# BMS-Shield_rev3.net
KiCad netlist of a schematic drawn in EAGLE
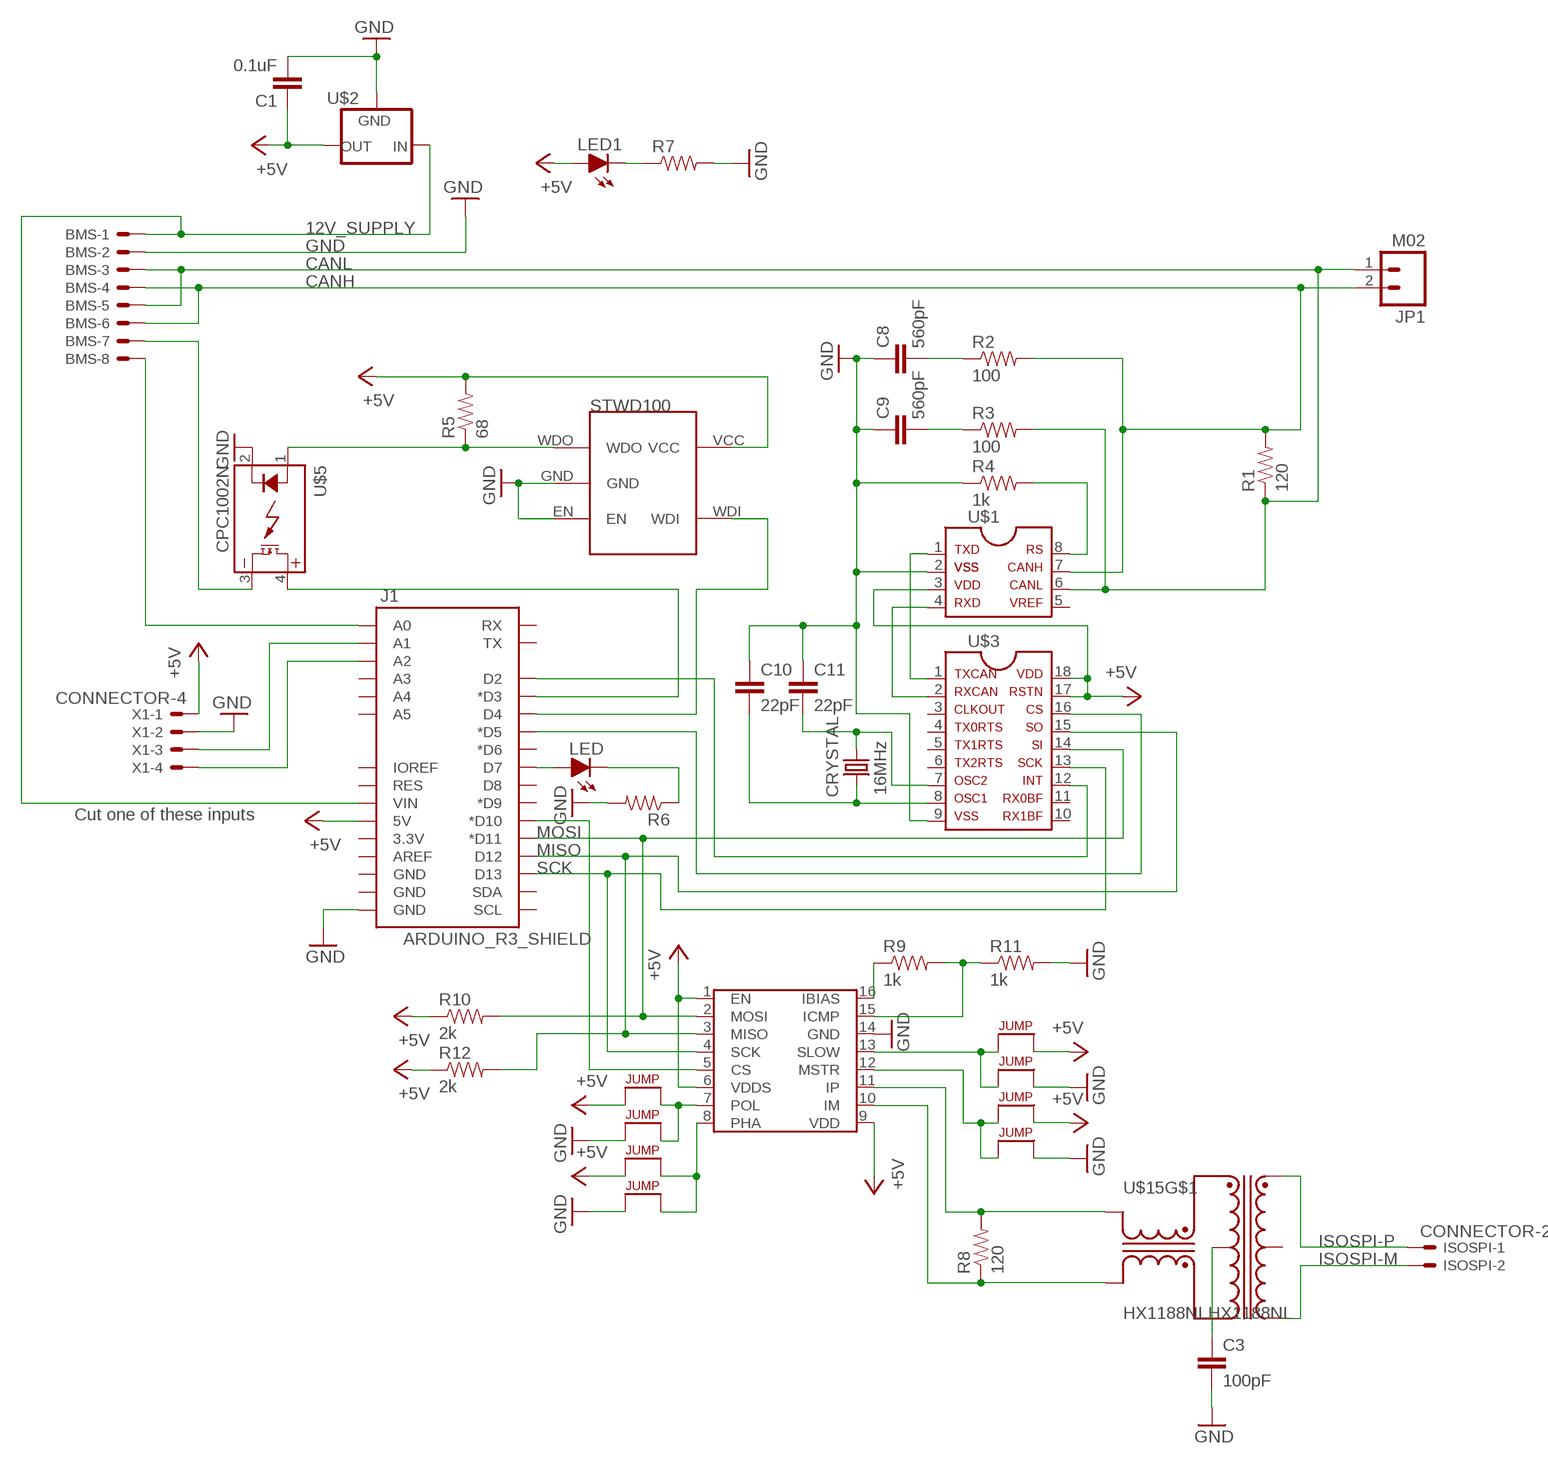
[diagram p0: schematic, sheet 1]

(export (version "E")
  (design (tool "Eeschema 10.0.6"))
  (components
    (comp (ref "BMS")
      (value "MINIFIT_5566-8")
      (footprint "eagle-import:MINIFIT_5566-8")
      (libsource (lib "eagle-import") (part "MINIFIT_5566-8"))
    )
    (comp (ref "C1")
      (value "0.1uF")
      (footprint "eagle-import:0805")
      (libsource (lib "eagle-import") (part "CAP0805"))
    )
    (comp (ref "C3")
      (value "100pF")
      (footprint "eagle-import:0805")
      (libsource (lib "eagle-import") (part "CAP0805"))
    )
    (comp (ref "C8")
      (value "560pF")
      (footprint "eagle-import:0805")
      (libsource (lib "eagle-import") (part "CAP0805"))
    )
    (comp (ref "C9")
      (value "560pF")
      (footprint "eagle-import:0805")
      (libsource (lib "eagle-import") (part "CAP0805"))
    )
    (comp (ref "C10")
      (value "22pF")
      (footprint "eagle-import:0805")
      (libsource (lib "eagle-import") (part "CAP0805"))
    )
    (comp (ref "C11")
      (value "22pF")
      (footprint "eagle-import:0805")
      (libsource (lib "eagle-import") (part "CAP0805"))
    )
    (comp (ref "CRYSTAL")
      (value "16MHz")
      (footprint "eagle-import:HC49UP")
      (libsource (lib "eagle-import") (part "CRYSTALSMD"))
    )
    (comp (ref "ISOSPI")
      (value "CONNECTOR-2")
      (footprint "eagle-import:MINIFIT_5566-2")
      (libsource (lib "eagle-import") (part "CONNECTOR-2"))
    )
    (comp (ref "J1")
      (value "ARDUINO_R3_SHIELD")
      (footprint "eagle-import:UNO_R3_SHIELD")
      (libsource (lib "eagle-import") (part "ARDUINO_R3_SHIELD"))
    )
    (comp (ref "JP1")
      (value "M02")
      (footprint "eagle-import:1X02")
      (libsource (lib "eagle-import") (part "M02"))
    )
    (comp (ref "LED")
      (value "LED-0805")
      (footprint "eagle-import:LED-805")
      (libsource (lib "eagle-import") (part "LED-0805"))
    )
    (comp (ref "LED1")
      (value "LED-0805")
      (footprint "eagle-import:LED-805")
      (libsource (lib "eagle-import") (part "LED-0805"))
    )
    (comp (ref "R1")
      (value "120")
      (footprint "eagle-import:0805")
      (libsource (lib "eagle-import") (part "RESISTOR0805-RES"))
    )
    (comp (ref "R2")
      (value "100")
      (footprint "eagle-import:0805")
      (libsource (lib "eagle-import") (part "RESISTOR0805-RES"))
    )
    (comp (ref "R3")
      (value "100")
      (footprint "eagle-import:0805")
      (libsource (lib "eagle-import") (part "RESISTOR0805-RES"))
    )
    (comp (ref "R4")
      (value "1k")
      (footprint "eagle-import:0805")
      (libsource (lib "eagle-import") (part "RESISTOR0805-RES"))
    )
    (comp (ref "R5")
      (value "68")
      (footprint "eagle-import:0805")
      (libsource (lib "eagle-import") (part "RESISTOR0805-RES"))
    )
    (comp (ref "R6")
      (value "RESISTOR0805-RES")
      (footprint "eagle-import:0805")
      (libsource (lib "eagle-import") (part "RESISTOR0805-RES"))
    )
    (comp (ref "R7")
      (value "RESISTOR0805-RES")
      (footprint "eagle-import:0805")
      (libsource (lib "eagle-import") (part "RESISTOR0805-RES"))
    )
    (comp (ref "R8")
      (value "120")
      (footprint "eagle-import:0805")
      (libsource (lib "eagle-import") (part "RESISTOR0805-RES"))
    )
    (comp (ref "R9")
      (value "1k")
      (footprint "eagle-import:0805")
      (libsource (lib "eagle-import") (part "RESISTOR0805-RES"))
    )
    (comp (ref "R10")
      (value "2k")
      (footprint "eagle-import:0805")
      (libsource (lib "eagle-import") (part "RESISTOR0805-RES"))
    )
    (comp (ref "R11")
      (value "1k")
      (footprint "eagle-import:0805")
      (libsource (lib "eagle-import") (part "RESISTOR0805-RES"))
    )
    (comp (ref "R12")
      (value "2k")
      (footprint "eagle-import:0805")
      (libsource (lib "eagle-import") (part "RESISTOR0805-RES"))
    )
    (comp (ref "U$1")
      (value "MCP2551")
      (footprint "eagle-import:SOIC-08")
      (libsource (lib "eagle-import") (part "MCP2551"))
    )
    (comp (ref "U$2")
      (value "5VREG_LM340-NLM340MPX-5.0/NOPB")
      (footprint "eagle-import:SOT223")
      (libsource (lib "eagle-import") (part "5VREG_LM340-NLM340MPX-5.0/NOPB"))
    )
    (comp (ref "U$3")
      (value "MCP2515SMD")
      (footprint "eagle-import:SOIC-18W")
      (libsource (lib "eagle-import") (part "MCP2515SMD"))
    )
    (comp (ref "U$4")
      (value "STWD100")
      (footprint "eagle-import:SOT23-5")
      (libsource (lib "eagle-import") (part "STWD100"))
    )
    (comp (ref "U$5")
      (value "CPC1002N")
      (footprint "eagle-import:SOP04")
      (libsource (lib "eagle-import") (part "CPC1002N"))
    )
    (comp (ref "U$6")
      (value "LTC6820")
      (footprint "eagle-import:MSOP-16")
      (libsource (lib "eagle-import") (part "LTC6820"))
    )
    (comp (ref "U$7")
      (value "JUMPER")
      (footprint "eagle-import:0805")
      (libsource (lib "eagle-import") (part "JUMPER"))
    )
    (comp (ref "U$8")
      (value "JUMPER")
      (footprint "eagle-import:0805")
      (libsource (lib "eagle-import") (part "JUMPER"))
    )
    (comp (ref "U$9")
      (value "JUMPER")
      (footprint "eagle-import:0805")
      (libsource (lib "eagle-import") (part "JUMPER"))
    )
    (comp (ref "U$10")
      (value "JUMPER")
      (footprint "eagle-import:0805")
      (libsource (lib "eagle-import") (part "JUMPER"))
    )
    (comp (ref "U$11")
      (value "JUMPER")
      (footprint "eagle-import:0805")
      (libsource (lib "eagle-import") (part "JUMPER"))
    )
    (comp (ref "U$12")
      (value "JUMPER")
      (footprint "eagle-import:0805")
      (libsource (lib "eagle-import") (part "JUMPER"))
    )
    (comp (ref "U$13")
      (value "JUMPER")
      (footprint "eagle-import:0805")
      (libsource (lib "eagle-import") (part "JUMPER"))
    )
    (comp (ref "U$14")
      (value "JUMPER")
      (footprint "eagle-import:0805")
      (libsource (lib "eagle-import") (part "JUMPER"))
    )
    (comp (ref "U$15")
      (value "HX1188NLHX1188NL")
      (footprint "eagle-import:HX1188NL")
      (libsource (lib "eagle-import") (part "HX1188NLHX1188NL"))
    )
    (comp (ref "X1")
      (value "CONNECTOR-4")
      (footprint "eagle-import:MINIFIT_5566-4")
      (libsource (lib "eagle-import") (part "CONNECTOR-4"))
    )
  )
  (nets
    (net (code "1") (name "+5V") (class "Default")
      (node (ref "C1") (pin "1") (pinfunction "1_1") (pintype "passive"))
      (node (ref "J1") (pin "5V") (pinfunction "5V_5V") (pintype "bidirectional"))
      (node (ref "LED1") (pin "A") (pinfunction "A_A") (pintype "passive"))
      (node (ref "R10") (pin "1") (pinfunction "1_1") (pintype "passive"))
      (node (ref "R12") (pin "1") (pinfunction "1_1") (pintype "passive"))
      (node (ref "R5") (pin "2") (pinfunction "2_2") (pintype "passive"))
      (node (ref "U$1") (pin "3") (pinfunction "3_3") (pintype "passive"))
      (node (ref "U$10") (pin "1") (pinfunction "P$1_1") (pintype "bidirectional"))
      (node (ref "U$11") (pin "2") (pinfunction "P$2_2") (pintype "bidirectional"))
      (node (ref "U$13") (pin "2") (pinfunction "P$2_2") (pintype "bidirectional"))
      (node (ref "U$2") (pin "3") (pinfunction "OUT_3") (pintype "output"))
      (node (ref "U$3") (pin "17") (pinfunction "17_17") (pintype "passive"))
      (node (ref "U$3") (pin "18") (pinfunction "18_18") (pintype "passive"))
      (node (ref "U$4") (pin "VCC") (pinfunction "VCC_VCC") (pintype "bidirectional"))
      (node (ref "U$6") (pin "1") (pinfunction "EN_1") (pintype "bidirectional"))
      (node (ref "U$6") (pin "6") (pinfunction "VDDS_6") (pintype "bidirectional"))
      (node (ref "U$6") (pin "9") (pinfunction "VDD_9") (pintype "bidirectional"))
      (node (ref "U$7") (pin "1") (pinfunction "P$1_1") (pintype "bidirectional"))
      (node (ref "X1") (pin "1") (pinfunction "S_1") (pintype "passive"))
    )
    (net (code "2") (name "/12V_SUPPLY") (class "Default")
      (node (ref "BMS") (pin "1") (pinfunction "S_1") (pintype "passive"))
      (node (ref "J1") (pin "VIN") (pinfunction "VIN_VIN") (pintype "bidirectional"))
      (node (ref "U$2") (pin "1") (pinfunction "IN_1") (pintype "input"))
    )
    (net (code "3") (name "/CANH") (class "Default")
      (node (ref "BMS") (pin "4") (pinfunction "S_4") (pintype "passive"))
      (node (ref "BMS") (pin "6") (pinfunction "S_6") (pintype "passive"))
      (node (ref "JP1") (pin "2") (pinfunction "2_2") (pintype "passive"))
      (node (ref "R1") (pin "2") (pinfunction "2_2") (pintype "passive"))
      (node (ref "R2") (pin "2") (pinfunction "2_2") (pintype "passive"))
      (node (ref "U$1") (pin "7") (pinfunction "7_7") (pintype "passive"))
    )
    (net (code "4") (name "/CANL") (class "Default")
      (node (ref "BMS") (pin "3") (pinfunction "S_3") (pintype "passive"))
      (node (ref "BMS") (pin "5") (pinfunction "S_5") (pintype "passive"))
      (node (ref "JP1") (pin "1") (pinfunction "1_1") (pintype "passive"))
      (node (ref "R1") (pin "1") (pinfunction "1_1") (pintype "passive"))
      (node (ref "R3") (pin "2") (pinfunction "2_2") (pintype "passive"))
      (node (ref "U$1") (pin "6") (pinfunction "6_6") (pintype "passive"))
    )
    (net (code "5") (name "/ISOSPI-M") (class "Default")
      (node (ref "ISOSPI") (pin "2") (pinfunction "S_2") (pintype "passive"))
      (node (ref "U$15") (pin "3") (pinfunction "D-_3") (pintype "passive"))
    )
    (net (code "6") (name "/ISOSPI-P") (class "Default")
      (node (ref "ISOSPI") (pin "1") (pinfunction "S_1") (pintype "passive"))
      (node (ref "U$15") (pin "1") (pinfunction "D+_1") (pintype "passive"))
    )
    (net (code "7") (name "/MISO") (class "Default")
      (node (ref "J1") (pin "D12") (pinfunction "D12_D12") (pintype "bidirectional"))
      (node (ref "R12") (pin "2") (pinfunction "2_2") (pintype "passive"))
      (node (ref "U$3") (pin "15") (pinfunction "15_15") (pintype "passive"))
      (node (ref "U$6") (pin "3") (pinfunction "MISO_3") (pintype "bidirectional"))
    )
    (net (code "8") (name "/MOSI") (class "Default")
      (node (ref "J1") (pin "D11") (pinfunction "*D11_D11") (pintype "bidirectional"))
      (node (ref "R10") (pin "2") (pinfunction "2_2") (pintype "passive"))
      (node (ref "U$3") (pin "14") (pinfunction "14_14") (pintype "passive"))
      (node (ref "U$6") (pin "2") (pinfunction "MOSI_2") (pintype "bidirectional"))
    )
    (net (code "9") (name "/SCK") (class "Default")
      (node (ref "J1") (pin "D13") (pinfunction "D13_D13") (pintype "bidirectional"))
      (node (ref "U$3") (pin "13") (pinfunction "13_13") (pintype "passive"))
      (node (ref "U$6") (pin "4") (pinfunction "SCK_4") (pintype "bidirectional"))
    )
    (net (code "10") (name "GND") (class "Default")
      (node (ref "BMS") (pin "2") (pinfunction "S_2") (pintype "passive"))
      (node (ref "C1") (pin "2") (pinfunction "2_2") (pintype "passive"))
      (node (ref "C10") (pin "1") (pinfunction "1_1") (pintype "passive"))
      (node (ref "C11") (pin "1") (pinfunction "1_1") (pintype "passive"))
      (node (ref "C3") (pin "2") (pinfunction "2_2") (pintype "passive"))
      (node (ref "C8") (pin "1") (pinfunction "1_1") (pintype "passive"))
      (node (ref "C9") (pin "1") (pinfunction "1_1") (pintype "passive"))
      (node (ref "J1") (pin "GND@0") (pinfunction "GND_GND@0") (pintype "bidirectional"))
      (node (ref "R11") (pin "2") (pinfunction "2_2") (pintype "passive"))
      (node (ref "R4") (pin "1") (pinfunction "1_1") (pintype "passive"))
      (node (ref "R6") (pin "2") (pinfunction "2_2") (pintype "passive"))
      (node (ref "R7") (pin "2") (pinfunction "2_2") (pintype "passive"))
      (node (ref "U$1") (pin "2") (pinfunction "2_2") (pintype "passive"))
      (node (ref "U$12") (pin "2") (pinfunction "P$2_2") (pintype "bidirectional"))
      (node (ref "U$14") (pin "2") (pinfunction "P$2_2") (pintype "bidirectional"))
      (node (ref "U$2") (pin "2") (pinfunction "GND_2") (pintype "input"))
      (node (ref "U$2") (pin "4") (pinfunction "GND_4") (pintype "input"))
      (node (ref "U$3") (pin "9") (pinfunction "9_9") (pintype "passive"))
      (node (ref "U$4") (pin "EN") (pinfunction "EN_EN") (pintype "bidirectional"))
      (node (ref "U$4") (pin "GND") (pinfunction "GND_GND") (pintype "bidirectional"))
      (node (ref "U$5") (pin "2") (pinfunction "CONTROL-_2") (pintype "passive"))
      (node (ref "U$6") (pin "14") (pinfunction "GND_14") (pintype "bidirectional"))
      (node (ref "U$8") (pin "1") (pinfunction "P$1_1") (pintype "bidirectional"))
      (node (ref "U$9") (pin "1") (pinfunction "P$1_1") (pintype "bidirectional"))
      (node (ref "X1") (pin "2") (pinfunction "S_2") (pintype "passive"))
    )
    (net (code "11") (name "Net-(BMSG-S)") (class "Default")
      (node (ref "BMS") (pin "7") (pinfunction "S_7") (pintype "passive"))
      (node (ref "U$5") (pin "3") (pinfunction "DC-_3") (pintype "passive"))
    )
    (net (code "12") (name "Net-(BMSH-S)") (class "Default")
      (node (ref "BMS") (pin "8") (pinfunction "S_8") (pintype "passive"))
      (node (ref "J1") (pin "A0") (pinfunction "A0_A0") (pintype "bidirectional"))
    )
    (net (code "13") (name "Net-(C8-Pad2)") (class "Default")
      (node (ref "C8") (pin "2") (pinfunction "2_2") (pintype "passive"))
      (node (ref "R2") (pin "1") (pinfunction "1_1") (pintype "passive"))
    )
    (net (code "14") (name "Net-(C9-Pad2)") (class "Default")
      (node (ref "C9") (pin "2") (pinfunction "2_2") (pintype "passive"))
      (node (ref "R3") (pin "1") (pinfunction "1_1") (pintype "passive"))
    )
    (net (code "15") (name "Net-(C10-Pad2)") (class "Default")
      (node (ref "C10") (pin "2") (pinfunction "2_2") (pintype "passive"))
      (node (ref "CRYSTAL") (pin "2") (pinfunction "2_2") (pintype "passive"))
      (node (ref "U$3") (pin "8") (pinfunction "8_8") (pintype "passive"))
    )
    (net (code "16") (name "Net-(C11-Pad2)") (class "Default")
      (node (ref "C11") (pin "2") (pinfunction "2_2") (pintype "passive"))
      (node (ref "CRYSTAL") (pin "1") (pinfunction "1_1") (pintype "passive"))
      (node (ref "U$3") (pin "7") (pinfunction "7_7") (pintype "passive"))
    )
    (net (code "17") (name "Net-(J1-*D3)") (class "Default")
      (node (ref "J1") (pin "D3") (pinfunction "*D3_D3") (pintype "bidirectional"))
      (node (ref "U$5") (pin "4") (pinfunction "DC+_4") (pintype "passive"))
    )
    (net (code "18") (name "Net-(J1-*D5)") (class "Default")
      (node (ref "J1") (pin "D5") (pinfunction "*D5_D5") (pintype "bidirectional"))
      (node (ref "U$3") (pin "16") (pinfunction "16_16") (pintype "passive"))
    )
    (net (code "19") (name "Net-(J1-*D10)") (class "Default")
      (node (ref "J1") (pin "D10") (pinfunction "*D10_D10") (pintype "bidirectional"))
      (node (ref "U$6") (pin "5") (pinfunction "CS_5") (pintype "bidirectional"))
    )
    (net (code "20") (name "Net-(J1-PadD2)") (class "Default")
      (node (ref "J1") (pin "D2") (pinfunction "D2_D2") (pintype "bidirectional"))
      (node (ref "U$3") (pin "12") (pinfunction "12_12") (pintype "passive"))
    )
    (net (code "21") (name "Net-(J1-PadD4)") (class "Default")
      (node (ref "J1") (pin "D4") (pinfunction "D4_D4") (pintype "bidirectional"))
      (node (ref "U$4") (pin "WDI") (pinfunction "WDI_WDI") (pintype "bidirectional"))
    )
    (net (code "22") (name "Net-(J1-PadD7)") (class "Default")
      (node (ref "J1") (pin "D7") (pinfunction "D7_D7") (pintype "bidirectional"))
      (node (ref "LED") (pin "A") (pinfunction "A_A") (pintype "passive"))
    )
    (net (code "23") (name "Net-(LED-PadC)") (class "Default")
      (node (ref "LED") (pin "C") (pinfunction "C_C") (pintype "passive"))
      (node (ref "R6") (pin "1") (pinfunction "1_1") (pintype "passive"))
    )
    (net (code "24") (name "Net-(LED1-PadC)") (class "Default")
      (node (ref "LED1") (pin "C") (pinfunction "C_C") (pintype "passive"))
      (node (ref "R7") (pin "1") (pinfunction "1_1") (pintype "passive"))
    )
    (net (code "25") (name "Net-(R4-Pad2)") (class "Default")
      (node (ref "R4") (pin "2") (pinfunction "2_2") (pintype "passive"))
      (node (ref "U$1") (pin "8") (pinfunction "8_8") (pintype "passive"))
    )
    (net (code "26") (name "Net-(U$1-Pad1)") (class "Default")
      (node (ref "U$1") (pin "1") (pinfunction "1_1") (pintype "passive"))
      (node (ref "U$3") (pin "1") (pinfunction "1_1") (pintype "passive"))
    )
    (net (code "27") (name "Net-(U$1-Pad4)") (class "Default")
      (node (ref "U$1") (pin "4") (pinfunction "4_4") (pintype "passive"))
      (node (ref "U$3") (pin "2") (pinfunction "2_2") (pintype "passive"))
    )
    (net (code "28") (name "Net-(U$5-CONTROL+)") (class "Default")
      (node (ref "R5") (pin "1") (pinfunction "1_1") (pintype "passive"))
      (node (ref "U$4") (pin "WDO") (pinfunction "WDO_WDO") (pintype "bidirectional"))
      (node (ref "U$5") (pin "1") (pinfunction "CONTROL+_1") (pintype "passive"))
    )
    (net (code "29") (name "Net-(U$6-IBIAS)") (class "Default")
      (node (ref "R9") (pin "1") (pinfunction "1_1") (pintype "passive"))
      (node (ref "U$6") (pin "16") (pinfunction "IBIAS_16") (pintype "bidirectional"))
    )
    (net (code "30") (name "Net-(U$6-ICMP)") (class "Default")
      (node (ref "R11") (pin "1") (pinfunction "1_1") (pintype "passive"))
      (node (ref "R9") (pin "2") (pinfunction "2_2") (pintype "passive"))
      (node (ref "U$6") (pin "15") (pinfunction "ICMP_15") (pintype "bidirectional"))
    )
    (net (code "31") (name "Net-(U$6-POL)") (class "Default")
      (node (ref "U$6") (pin "7") (pinfunction "POL_7") (pintype "bidirectional"))
      (node (ref "U$7") (pin "2") (pinfunction "P$2_2") (pintype "bidirectional"))
      (node (ref "U$8") (pin "2") (pinfunction "P$2_2") (pintype "bidirectional"))
    )
    (net (code "32") (name "Net-(U$10-P$2)") (class "Default")
      (node (ref "U$10") (pin "2") (pinfunction "P$2_2") (pintype "bidirectional"))
      (node (ref "U$6") (pin "8") (pinfunction "PHA_8") (pintype "bidirectional"))
      (node (ref "U$9") (pin "2") (pinfunction "P$2_2") (pintype "bidirectional"))
    )
    (net (code "33") (name "Net-(U$11-P$1)") (class "Default")
      (node (ref "U$11") (pin "1") (pinfunction "P$1_1") (pintype "bidirectional"))
      (node (ref "U$12") (pin "1") (pinfunction "P$1_1") (pintype "bidirectional"))
      (node (ref "U$6") (pin "13") (pinfunction "SLOW_13") (pintype "bidirectional"))
    )
    (net (code "34") (name "Net-(U$13-P$1)") (class "Default")
      (node (ref "U$13") (pin "1") (pinfunction "P$1_1") (pintype "bidirectional"))
      (node (ref "U$14") (pin "1") (pinfunction "P$1_1") (pintype "bidirectional"))
      (node (ref "U$6") (pin "12") (pinfunction "MSTR_12") (pintype "bidirectional"))
    )
    (net (code "35") (name "Net-(U$15A-CX)") (class "Default")
      (node (ref "C3") (pin "1") (pinfunction "1_1") (pintype "passive"))
      (node (ref "U$15") (pin "15") (pinfunction "CX_15") (pintype "passive"))
    )
    (net (code "36") (name "Net-(U$15A-X+)") (class "Default")
      (node (ref "R8") (pin "2") (pinfunction "2_2") (pintype "passive"))
      (node (ref "U$15") (pin "16") (pinfunction "X+_16") (pintype "passive"))
      (node (ref "U$6") (pin "11") (pinfunction "IP_11") (pintype "bidirectional"))
    )
    (net (code "37") (name "Net-(U$15A-X-)") (class "Default")
      (node (ref "R8") (pin "1") (pinfunction "1_1") (pintype "passive"))
      (node (ref "U$15") (pin "14") (pinfunction "X-_14") (pintype "passive"))
      (node (ref "U$6") (pin "10") (pinfunction "IM_10") (pintype "bidirectional"))
    )
    (net (code "38") (name "Net-(X1C-S)") (class "Default")
      (node (ref "J1") (pin "A1") (pinfunction "A1_A1") (pintype "bidirectional"))
      (node (ref "X1") (pin "3") (pinfunction "S_3") (pintype "passive"))
    )
    (net (code "39") (name "Net-(X1D-S)") (class "Default")
      (node (ref "J1") (pin "A2") (pinfunction "A2_A2") (pintype "bidirectional"))
      (node (ref "X1") (pin "4") (pinfunction "S_4") (pintype "passive"))
    )
    (net (code "40") (name "unconnected-(J1-*D6-PadD6)") (class "Default")
      (node (ref "J1") (pin "D6") (pinfunction "*D6_D6") (pintype "bidirectional"))
    )
    (net (code "41") (name "unconnected-(J1-*D9-PadD9)") (class "Default")
      (node (ref "J1") (pin "D9") (pinfunction "*D9_D9") (pintype "bidirectional"))
    )
    (net (code "42") (name "unconnected-(J1-GND-PadGND@1)") (class "Default")
      (node (ref "J1") (pin "GND@1") (pinfunction "GND_GND@1") (pintype "bidirectional"))
    )
    (net (code "43") (name "unconnected-(J1-GND-PadGND@2)") (class "Default")
      (node (ref "J1") (pin "GND@2") (pinfunction "GND_GND@2") (pintype "bidirectional"))
    )
    (net (code "44") (name "unconnected-(J1-Pad3.3V)") (class "Default")
      (node (ref "J1") (pin "3.3V") (pinfunction "3.3V_3.3V") (pintype "bidirectional"))
    )
    (net (code "45") (name "unconnected-(J1-PadA3)") (class "Default")
      (node (ref "J1") (pin "A3") (pinfunction "A3_A3") (pintype "bidirectional"))
    )
    (net (code "46") (name "unconnected-(J1-PadA4)") (class "Default")
      (node (ref "J1") (pin "A4") (pinfunction "A4_A4") (pintype "bidirectional"))
    )
    (net (code "47") (name "unconnected-(J1-PadA5)") (class "Default")
      (node (ref "J1") (pin "A5") (pinfunction "A5_A5") (pintype "bidirectional"))
    )
    (net (code "48") (name "unconnected-(J1-PadAREF)") (class "Default")
      (node (ref "J1") (pin "AREF") (pinfunction "AREF_AREF") (pintype "bidirectional"))
    )
    (net (code "49") (name "unconnected-(J1-PadD8)") (class "Default")
      (node (ref "J1") (pin "D8") (pinfunction "D8_D8") (pintype "bidirectional"))
    )
    (net (code "50") (name "unconnected-(J1-PadIOREF)") (class "Default")
      (node (ref "J1") (pin "IOREF") (pinfunction "IOREF_IOREF") (pintype "bidirectional"))
    )
    (net (code "51") (name "unconnected-(J1-PadRES)") (class "Default")
      (node (ref "J1") (pin "RES") (pinfunction "RES_RES") (pintype "bidirectional"))
    )
    (net (code "52") (name "unconnected-(J1-PadRX)") (class "Default")
      (node (ref "J1") (pin "RX") (pinfunction "RX_RX") (pintype "bidirectional"))
    )
    (net (code "53") (name "unconnected-(J1-PadSCL)") (class "Default")
      (node (ref "J1") (pin "SCL") (pinfunction "SCL_SCL") (pintype "bidirectional"))
    )
    (net (code "54") (name "unconnected-(J1-PadSDA)") (class "Default")
      (node (ref "J1") (pin "SDA") (pinfunction "SDA_SDA") (pintype "bidirectional"))
    )
    (net (code "55") (name "unconnected-(J1-PadTX)") (class "Default")
      (node (ref "J1") (pin "TX") (pinfunction "TX_TX") (pintype "bidirectional"))
    )
    (net (code "56") (name "unconnected-(U$1-Pad5)") (class "Default")
      (node (ref "U$1") (pin "5") (pinfunction "5_5") (pintype "passive"))
    )
    (net (code "57") (name "unconnected-(U$3-Pad3)") (class "Default")
      (node (ref "U$3") (pin "3") (pinfunction "3_3") (pintype "passive"))
    )
    (net (code "58") (name "unconnected-(U$3-Pad4)") (class "Default")
      (node (ref "U$3") (pin "4") (pinfunction "4_4") (pintype "passive"))
    )
    (net (code "59") (name "unconnected-(U$3-Pad5)") (class "Default")
      (node (ref "U$3") (pin "5") (pinfunction "5_5") (pintype "passive"))
    )
    (net (code "60") (name "unconnected-(U$3-Pad6)") (class "Default")
      (node (ref "U$3") (pin "6") (pinfunction "6_6") (pintype "passive"))
    )
    (net (code "61") (name "unconnected-(U$3-Pad10)") (class "Default")
      (node (ref "U$3") (pin "10") (pinfunction "10_10") (pintype "passive"))
    )
    (net (code "62") (name "unconnected-(U$3-Pad11)") (class "Default")
      (node (ref "U$3") (pin "11") (pinfunction "11_11") (pintype "passive"))
    )
    (net (code "63") (name "unconnected-(U$15A-CD-Pad2)") (class "Default")
      (node (ref "U$15") (pin "2") (pinfunction "CD_2") (pintype "passive"))
    )
  )
)
